# US_SB_MCU.net
KiCad netlist of a schematic drawn in Altium Designer
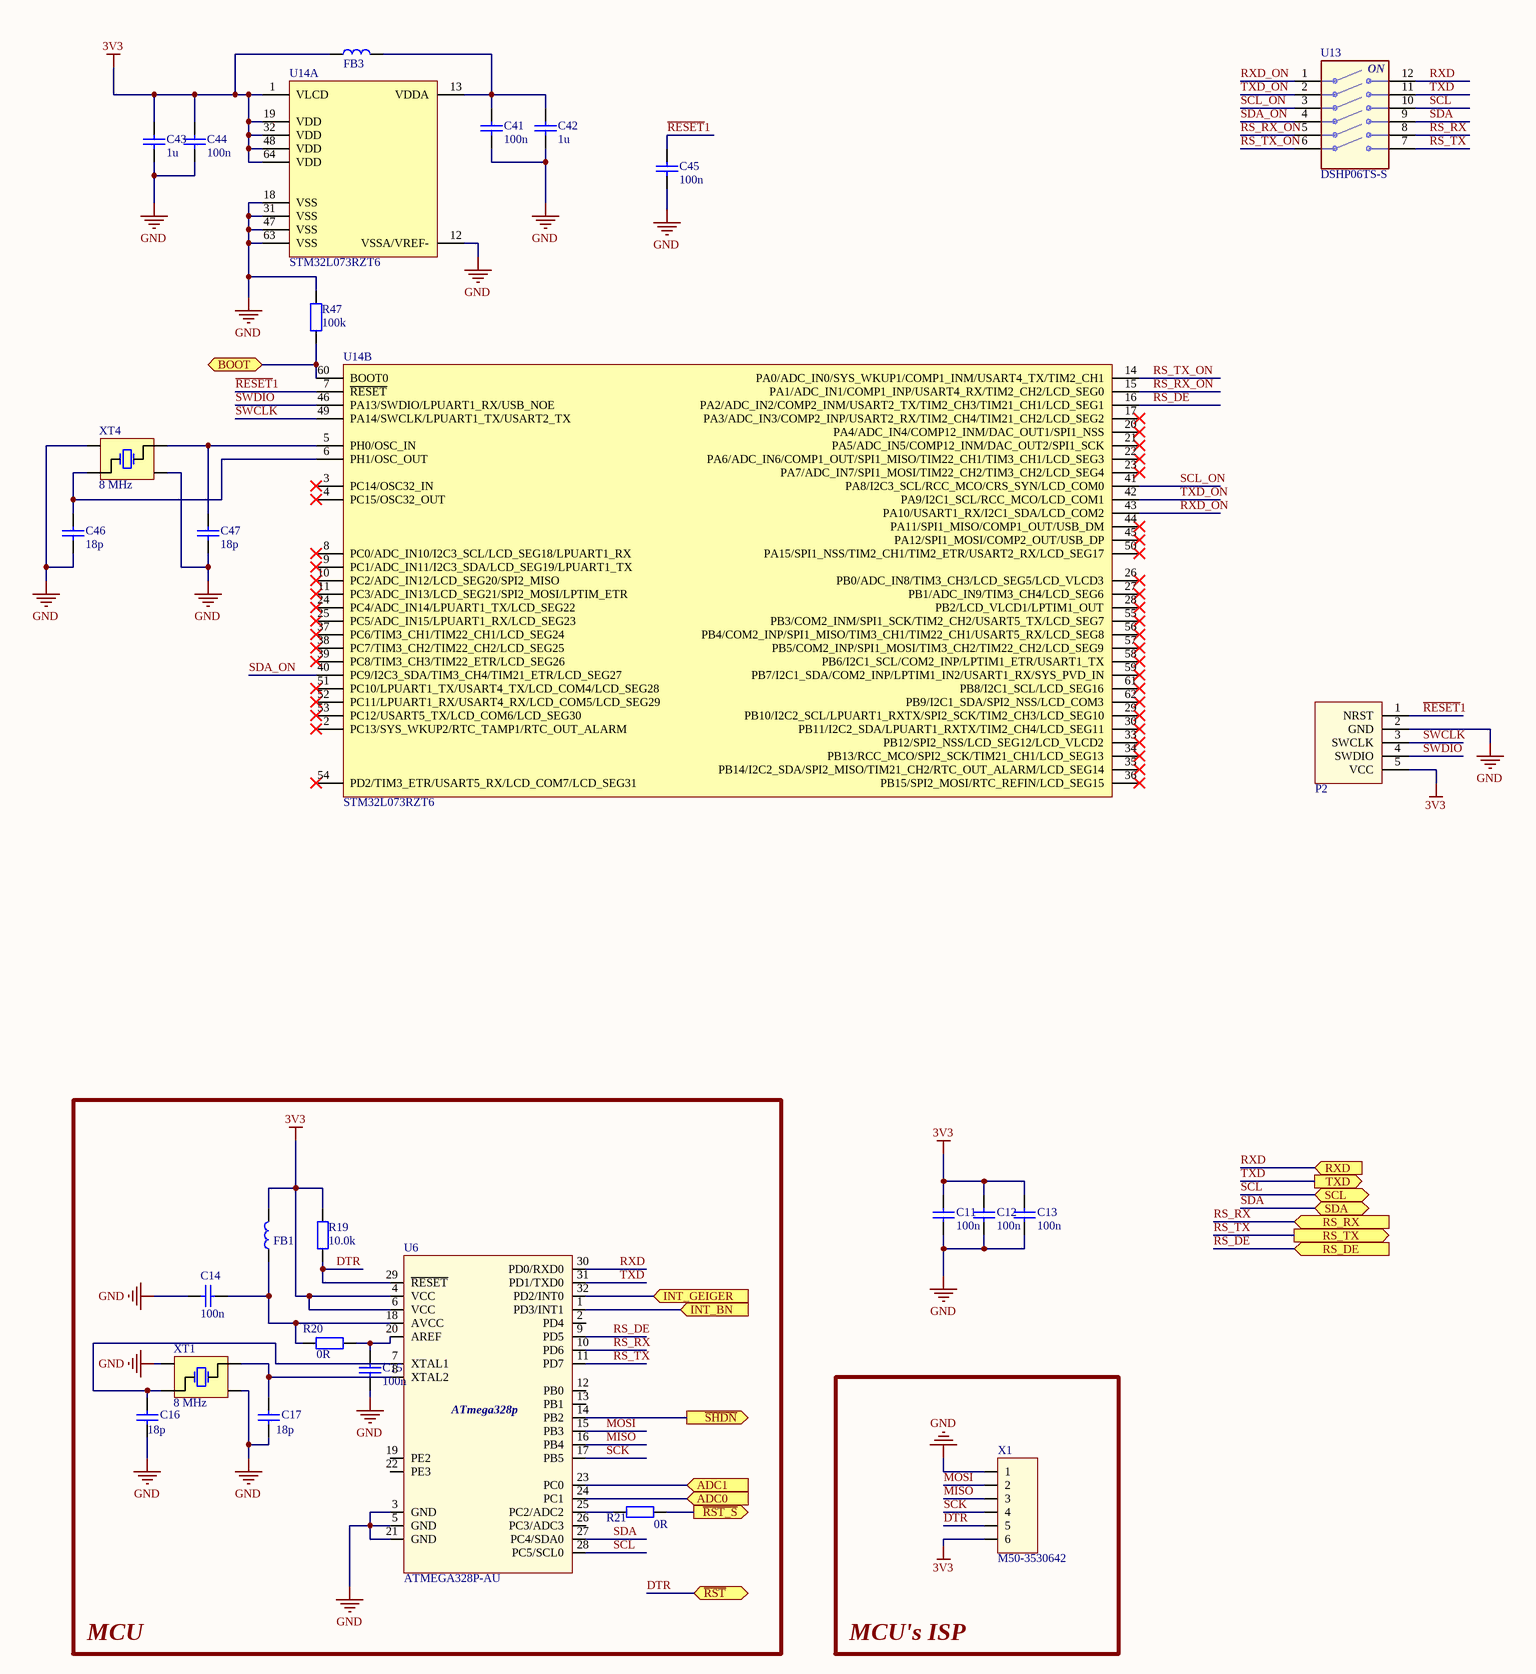
[diagram p0: US_SB_MCU.SchDoc]

(export (version "E")
  (design (tool "Eeschema 10.0.6"))
  (components
    (comp (ref "C11")
      (value "100n")
      (footprint "C0603_IPC_HD")
      (description "CAP CER 0.1UF 16V X7R 0603")
      (fields
        (field (name "MANUFACTURER") "Samsung Electro-Mechanics")
        (field (name "MANUFACTURER PART NUMBER") "CL10B104KO8NNNC")
      )
      (libsource (lib "alfasat_parts_lib") (part "CL10B104KO8NNNC"))
    )
    (comp (ref "C12")
      (value "100n")
      (footprint "C0603_IPC_HD")
      (description "CAP CER 0.1UF 16V X7R 0603")
      (fields
        (field (name "MANUFACTURER") "Samsung Electro-Mechanics")
        (field (name "MANUFACTURER PART NUMBER") "CL10B104KO8NNNC")
      )
      (libsource (lib "alfasat_parts_lib") (part "CL10B104KO8NNNC"))
    )
    (comp (ref "C13")
      (value "100n")
      (footprint "C0603_IPC_HD")
      (description "CAP CER 0.1UF 16V X7R 0603")
      (fields
        (field (name "MANUFACTURER") "Samsung Electro-Mechanics")
        (field (name "MANUFACTURER PART NUMBER") "CL10B104KO8NNNC")
      )
      (libsource (lib "alfasat_parts_lib") (part "CL10B104KO8NNNC"))
    )
    (comp (ref "C14")
      (value "100n")
      (footprint "C0603_IPC_HD")
      (description "CAP CER 0.1UF 16V X7R 0603")
      (fields
        (field (name "MANUFACTURER") "Samsung Electro-Mechanics")
        (field (name "MANUFACTURER PART NUMBER") "CL10B104KO8NNNC")
      )
      (libsource (lib "alfasat_parts_lib") (part "CL10B104KO8NNNC"))
    )
    (comp (ref "C15")
      (value "100n")
      (footprint "C0603_IPC_HD")
      (description "CAP CER 0.1UF 16V X7R 0603")
      (fields
        (field (name "MANUFACTURER") "Samsung Electro-Mechanics")
        (field (name "MANUFACTURER PART NUMBER") "CL10B104KO8NNNC")
      )
      (libsource (lib "alfasat_parts_lib") (part "CL10B104KO8NNNC"))
    )
    (comp (ref "C16")
      (value "18p")
      (footprint "C0603_IPC_HD")
      (description "CAP CER 18PF 50V C0G/NP0 0603")
      (fields
        (field (name "MANUFACTURER") "Samsung Electro-Mechanics")
        (field (name "MANUFACTURER PART NUMBER") "CL10C180JB8NNNC")
      )
      (libsource (lib "alfasat_lib") (part "CL10C180JB8NNNC"))
    )
    (comp (ref "C17")
      (value "18p")
      (footprint "C0603_IPC_HD")
      (description "CAP CER 18PF 50V C0G/NP0 0603")
      (fields
        (field (name "MANUFACTURER") "Samsung Electro-Mechanics")
        (field (name "MANUFACTURER PART NUMBER") "CL10C180JB8NNNC")
      )
      (libsource (lib "alfasat_lib") (part "CL10C180JB8NNNC"))
    )
    (comp (ref "C41")
      (value "100n")
      (footprint "C0603_IPC_HD")
      (description "CAP CER 0.1UF 16V X7R 0603")
      (fields
        (field (name "MANUFACTURER") "Samsung Electro-Mechanics")
        (field (name "MANUFACTURER PART NUMBER") "CL10B104KO8NNNC")
      )
      (libsource (lib "alfasat_parts_lib") (part "CL10B104KO8NNNC"))
    )
    (comp (ref "C42")
      (value "1u")
      (footprint "C0603_IPC_HD")
      (description "CAP CER 1UF 16V X7R 0603")
      (fields
        (field (name "MANUFACTURER") "Samsung Electro-Mechanics")
        (field (name "MANUFACTURER PART NUMBER") "CL10B105MO8NNWC")
      )
      (libsource (lib "alfasat_parts_lib") (part "CL10B105MO8NNWC"))
    )
    (comp (ref "C43")
      (value "1u")
      (footprint "C0603_IPC_HD")
      (description "CAP CER 1UF 16V X7R 0603")
      (fields
        (field (name "MANUFACTURER") "Samsung Electro-Mechanics")
        (field (name "MANUFACTURER PART NUMBER") "CL10B105MO8NNWC")
      )
      (libsource (lib "alfasat_parts_lib") (part "CL10B105MO8NNWC"))
    )
    (comp (ref "C44")
      (value "100n")
      (footprint "C0603_IPC_HD")
      (description "CAP CER 0.1UF 16V X7R 0603")
      (fields
        (field (name "MANUFACTURER") "Samsung Electro-Mechanics")
        (field (name "MANUFACTURER PART NUMBER") "CL10B104KO8NNNC")
      )
      (libsource (lib "alfasat_parts_lib") (part "CL10B104KO8NNNC"))
    )
    (comp (ref "C45")
      (value "100n")
      (footprint "C0603_IPC_HD")
      (description "CAP CER 0.1UF 16V X7R 0603")
      (fields
        (field (name "MANUFACTURER") "Samsung Electro-Mechanics")
        (field (name "MANUFACTURER PART NUMBER") "CL10B104KO8NNNC")
      )
      (libsource (lib "alfasat_parts_lib") (part "CL10B104KO8NNNC"))
    )
    (comp (ref "C46")
      (value "18p")
      (footprint "C0603_IPC_HD")
      (description "CAP CER 18PF 50V C0G/NP0 0603")
      (fields
        (field (name "MANUFACTURER") "Samsung Electro-Mechanics")
        (field (name "MANUFACTURER PART NUMBER") "CL10C180JB8NNNC")
      )
      (libsource (lib "alfasat_parts_lib") (part "CL10C180JB8NNNC"))
    )
    (comp (ref "C47")
      (value "18p")
      (footprint "C0603_IPC_HD")
      (description "CAP CER 18PF 50V C0G/NP0 0603")
      (fields
        (field (name "MANUFACTURER") "Samsung Electro-Mechanics")
        (field (name "MANUFACTURER PART NUMBER") "CL10C180JB8NNNC")
      )
      (libsource (lib "alfasat_parts_lib") (part "CL10C180JB8NNNC"))
    )
    (comp (ref "FB1")
      (value "MH1608-601Y")
      (footprint "L0603_IPC_MD")
      (description "FERRITE BEAD 600R@100MHz 0603 for Power Line, 1000mA")
      (fields (field (name "MANUFACTURER") "Bourns Inc."))
      (libsource (lib "alfasat_lib") (part "MH1608-601Y"))
    )
    (comp (ref "FB3")
      (value "MH1608-601Y")
      (footprint "L0603_IPC_MD")
      (description "FERRITE BEAD 600R@100MHz 0603 for Power Line, 1000mA")
      (fields (field (name "MANUFACTURER") "Bourns Inc."))
      (libsource (lib "alfasat_parts_lib") (part "MH1608-601Y"))
    )
    (comp (ref "P2")
      (value "SWD")
      (footprint "SWD_CON_VAR1")
      (description "SWDIO SWCLK VDD GND NRST")
      (libsource (lib "alfasat_parts_lib") (part "SWD-CONNECTOR_VAR1"))
    )
    (comp (ref "R19")
      (value "10.0k")
      (footprint "R0603_IPC_MD")
      (description "RES 10K OHM 1% 1/10W 0603")
      (fields
        (field (name "MANUFACTURER") "Stackpole Electronics Inc")
        (field (name "MANUFACTURER PART NUMBER") "RMCF0603FT10K0")
      )
      (libsource (lib "alfasat_parts_lib") (part "RMCF0603FT10K0"))
    )
    (comp (ref "R20")
      (value "0R")
      (footprint "R0603_IPC_MD")
      (description "RES SMD 0 OHM JUMPER 1/10W 0603")
      (fields
        (field (name "MANUFACTURER") "Bourns Inc.")
        (field (name "MANUFACTURER PART NUMBER") "CR0603-J/-000ELF")
      )
      (libsource (lib "alfasat_lib") (part "CR0603-J/-000ELF"))
    )
    (comp (ref "R21")
      (value "0R")
      (footprint "R0603_IPC_MD")
      (description "RES SMD 0 OHM JUMPER 1/10W 0603")
      (fields
        (field (name "MANUFACTURER") "Bourns Inc.")
        (field (name "MANUFACTURER PART NUMBER") "CR0603-J/-000ELF")
      )
      (libsource (lib "alfasat_parts_lib") (part "CR0603-J/-000ELF"))
    )
    (comp (ref "R47")
      (value "100k")
      (footprint "R0603_IPC_MD")
      (description "RES SMD 100K OHM 5% 1/10W 0603")
      (fields
        (field (name "MANUFACTURER") "Bourns Inc.")
        (field (name "MANUFACTURER PART NUMBER") "CR0603-JW-104ELF")
      )
      (libsource (lib "alfasat_parts_lib") (part "CR0603-JW-104ELF"))
    )
    (comp (ref "U6")
      (value "ATMEGA328P-AU")
      (footprint "ATmega328P_TQFP80P900X900X120-32N")
      (description "AVR AVR® ATmega Microcontroller IC 8-Bit 20MHz 32KB (16K x 16) FLASH 32-TQFP (7x7)")
      (fields (field (name "MANUFACTURER") "Microchip Technology"))
      (libsource (lib "alfasat_lib_eps") (part "ATMEGA328P-AU"))
    )
    (comp (ref "U13")
      (value "DSHP06TS-S")
      (footprint "SOIC_SW_SOIC127P850X235-12N")
      (description "SPST 6 1.27mm, Half Slide (Standard) Black SMD DIP Switches RoHS")
      (fields (field (name "MANUFACTURER") "XKB Enterprise"))
      (libsource (lib "alfasat_lib_eps") (part "DSHP06TS-S"))
    )
    (comp (ref "U14")
      (value "STM32L073RZT6")
      (footprint "LQFP64_10X10MM")
      (description "Ultra-low-power 32-bit MCU ARM®-based Cortex®-M0+")
      (fields (field (name "MANUFACTURER") "ST"))
      (libsource (lib "alfasat_parts_lib") (part "STM32L073RZT6"))
    )
    (comp (ref "X1")
      (value "M50-3530642")
      (footprint "PLS_1X6_1.27")
      (description "CONN HEADER VERT 6POS 1.27MM")
      (fields (field (name "MANUFACTURER") "Harwin Inc."))
      (libsource (lib "alfasat_lib_eps") (part "PLD_1X6_1.27"))
    )
    (comp (ref "XT1")
      (value "8 MHz")
      (footprint "5.0X3.2_4PAD_SMT")
      (description "8MHz ±10ppm Crystal 10pF 200 Ohms 4-SMD, No Lead")
      (fields
        (field (name "MANUFACTURER PART NUMBER") "ABM3B-8.000MHZ-10-1-U-T")
        (field (name "MANUFACTURER") "Abracon LLC")
      )
      (libsource (lib "alfasat_parts_lib") (part "ABM3B-8.000MHZ-10-1-U-T"))
    )
    (comp (ref "XT4")
      (value "8 MHz")
      (footprint "5.0X3.2_4PAD_SMT")
      (description "8MHz ±10ppm Crystal 10pF 200 Ohms 4-SMD, No Lead")
      (fields
        (field (name "MANUFACTURER PART NUMBER") "ABM3B-8.000MHZ-10-1-U-T")
        (field (name "MANUFACTURER") "Abracon LLC")
      )
      (libsource (lib "alfasat_parts_lib") (part "ABM3B-8.000MHZ-10-1-U-T"))
    )
  )
  (nets
    (net (code "1") (name "/ADC0") (class "Default")
      (node (ref "U6") (pin "24") (pinfunction "PC1_24") (pintype "passive"))
    )
    (net (code "2") (name "/ADC1") (class "Default")
      (node (ref "U6") (pin "23") (pinfunction "PC0_23") (pintype "passive"))
    )
    (net (code "3") (name "/BOOT") (class "Default")
      (node (ref "R47") (pin "1") (pinfunction "1_1") (pintype "passive"))
      (node (ref "U14") (pin "60") (pinfunction "BOOT0_60") (pintype "passive"))
    )
    (net (code "4") (name "/DTR") (class "Default")
      (node (ref "R19") (pin "1") (pinfunction "1_1") (pintype "passive"))
      (node (ref "U6") (pin "29") (pinfunction "~{RESET}_29") (pintype "passive"))
      (node (ref "X1") (pin "5") (pinfunction "5_5") (pintype "passive"))
    )
    (net (code "5") (name "/INT_BN") (class "Default")
      (node (ref "U6") (pin "1") (pinfunction "PD3/INT1_1") (pintype "passive"))
    )
    (net (code "6") (name "/INT_GEIGER") (class "Default")
      (node (ref "U6") (pin "32") (pinfunction "PD2/INT0_32") (pintype "passive"))
    )
    (net (code "7") (name "/MISO") (class "Default")
      (node (ref "U6") (pin "16") (pinfunction "PB4_16") (pintype "passive"))
      (node (ref "X1") (pin "3") (pinfunction "3_3") (pintype "passive"))
    )
    (net (code "8") (name "/MOSI") (class "Default")
      (node (ref "U6") (pin "15") (pinfunction "PB3_15") (pintype "passive"))
      (node (ref "X1") (pin "2") (pinfunction "2_2") (pintype "passive"))
    )
    (net (code "9") (name "/RS_DE") (class "Default")
      (node (ref "U14") (pin "16") (pinfunction "PA2/ADC_IN2/COMP2_INM/USART2_TX/TIM2_CH3/TIM21_CH1/LCD_SEG1_16") (pintype "passive"))
      (node (ref "U6") (pin "9") (pinfunction "PD5_9") (pintype "passive"))
    )
    (net (code "10") (name "/RS_RX") (class "Default")
      (node (ref "U13") (pin "8") (pinfunction "8_8") (pintype "passive"))
      (node (ref "U6") (pin "10") (pinfunction "PD6_10") (pintype "passive"))
    )
    (net (code "11") (name "/RS_RX_ON") (class "Default")
      (node (ref "U13") (pin "5") (pinfunction "5_5") (pintype "passive"))
      (node (ref "U14") (pin "15") (pinfunction "PA1/ADC_IN1/COMP1_INP/USART4_RX/TIM2_CH2/LCD_SEG0_15") (pintype "passive"))
    )
    (net (code "12") (name "/RS_TX") (class "Default")
      (node (ref "U13") (pin "7") (pinfunction "7_7") (pintype "passive"))
      (node (ref "U6") (pin "11") (pinfunction "PD7_11") (pintype "passive"))
    )
    (net (code "13") (name "/RS_TX_ON") (class "Default")
      (node (ref "U13") (pin "6") (pinfunction "6_6") (pintype "passive"))
      (node (ref "U14") (pin "14") (pinfunction "PA0/ADC_IN0/SYS_WKUP1/COMP1_INM/USART4_TX/TIM2_CH1_14") (pintype "passive"))
    )
    (net (code "14") (name "/RXD") (class "Default")
      (node (ref "U13") (pin "12") (pinfunction "12_12") (pintype "passive"))
      (node (ref "U6") (pin "30") (pinfunction "PD0/RXD0_30") (pintype "passive"))
    )
    (net (code "15") (name "/RXD_ON") (class "Default")
      (node (ref "U13") (pin "1") (pinfunction "1_1") (pintype "passive"))
      (node (ref "U14") (pin "43") (pinfunction "PA10/USART1_RX/I2C1_SDA/LCD_COM2_43") (pintype "passive"))
    )
    (net (code "16") (name "/SCK") (class "Default")
      (node (ref "U6") (pin "17") (pinfunction "PB5_17") (pintype "passive"))
      (node (ref "X1") (pin "4") (pinfunction "4_4") (pintype "passive"))
    )
    (net (code "17") (name "/SCL") (class "Default")
      (node (ref "U13") (pin "10") (pinfunction "10_10") (pintype "passive"))
      (node (ref "U6") (pin "28") (pinfunction "PC5/SCL0_28") (pintype "passive"))
    )
    (net (code "18") (name "/SCL_ON") (class "Default")
      (node (ref "U13") (pin "3") (pinfunction "3_3") (pintype "passive"))
      (node (ref "U14") (pin "41") (pinfunction "PA8/I2C3_SCL/RCC_MCO/CRS_SYN/LCD_COM0_41") (pintype "passive"))
    )
    (net (code "19") (name "/SDA") (class "Default")
      (node (ref "U13") (pin "9") (pinfunction "9_9") (pintype "passive"))
      (node (ref "U6") (pin "27") (pinfunction "PC4/SDA0_27") (pintype "passive"))
    )
    (net (code "20") (name "/SDA_ON") (class "Default")
      (node (ref "U13") (pin "4") (pinfunction "4_4") (pintype "passive"))
      (node (ref "U14") (pin "40") (pinfunction "PC9/I2C3_SDA/TIM3_CH4/TIM21_ETR/LCD_SEG27_40") (pintype "passive"))
    )
    (net (code "21") (name "/SWCLK") (class "Default")
      (node (ref "P2") (pin "3") (pinfunction "SWCLK_3") (pintype "passive"))
      (node (ref "U14") (pin "49") (pinfunction "PA14/SWCLK/LPUART1_TX/USART2_TX_49") (pintype "passive"))
    )
    (net (code "22") (name "/SWDIO") (class "Default")
      (node (ref "P2") (pin "4") (pinfunction "SWDIO_4") (pintype "passive"))
      (node (ref "U14") (pin "46") (pinfunction "PA13/SWDIO/LPUART1_RX/USB_NOE_46") (pintype "passive"))
    )
    (net (code "23") (name "/TXD") (class "Default")
      (node (ref "U13") (pin "11") (pinfunction "11_11") (pintype "passive"))
      (node (ref "U6") (pin "31") (pinfunction "PD1/TXD0_31") (pintype "passive"))
    )
    (net (code "24") (name "/TXD_ON") (class "Default")
      (node (ref "U13") (pin "2") (pinfunction "2_2") (pintype "passive"))
      (node (ref "U14") (pin "42") (pinfunction "PA9/I2C1_SCL/RCC_MCO/LCD_COM1_42") (pintype "passive"))
    )
    (net (code "25") (name "/~{RESET}1") (class "Default")
      (node (ref "C45") (pin "1") (pinfunction "1_1") (pintype "passive"))
      (node (ref "P2") (pin "1") (pinfunction "NRST_1") (pintype "passive"))
      (node (ref "U14") (pin "7") (pinfunction "~{RESET}_7") (pintype "passive"))
    )
    (net (code "26") (name "/~{RST_S}") (class "Default")
      (node (ref "R21") (pin "2") (pinfunction "2_2") (pintype "passive"))
    )
    (net (code "27") (name "/~{SHDN}") (class "Default")
      (node (ref "U6") (pin "14") (pinfunction "PB2_14") (pintype "passive"))
    )
    (net (code "28") (name "3V3") (class "Default")
      (node (ref "C11") (pin "1") (pinfunction "1_1") (pintype "passive"))
      (node (ref "C12") (pin "1") (pinfunction "1_1") (pintype "passive"))
      (node (ref "C13") (pin "1") (pinfunction "1_1") (pintype "passive"))
      (node (ref "C43") (pin "2") (pinfunction "2_2") (pintype "passive"))
      (node (ref "C44") (pin "2") (pinfunction "2_2") (pintype "passive"))
      (node (ref "FB1") (pin "2") (pinfunction "2_2") (pintype "passive"))
      (node (ref "FB3") (pin "1") (pinfunction "1_1") (pintype "passive"))
      (node (ref "P2") (pin "5") (pinfunction "VCC_5") (pintype "passive"))
      (node (ref "R19") (pin "2") (pinfunction "2_2") (pintype "passive"))
      (node (ref "U14") (pin "1") (pinfunction "VLCD_1") (pintype "power_in"))
      (node (ref "U14") (pin "19") (pinfunction "VDD_19") (pintype "power_in"))
      (node (ref "U14") (pin "32") (pinfunction "VDD_32") (pintype "power_in"))
      (node (ref "U14") (pin "48") (pinfunction "VDD_48") (pintype "power_in"))
      (node (ref "U14") (pin "64") (pinfunction "VDD_64") (pintype "power_in"))
      (node (ref "U6") (pin "4") (pinfunction "VCC_4") (pintype "passive"))
      (node (ref "U6") (pin "6") (pinfunction "VCC_6") (pintype "passive"))
      (node (ref "X1") (pin "6") (pinfunction "6_6") (pintype "passive"))
    )
    (net (code "29") (name "GND") (class "Default")
      (node (ref "C11") (pin "2") (pinfunction "2_2") (pintype "passive"))
      (node (ref "C12") (pin "2") (pinfunction "2_2") (pintype "passive"))
      (node (ref "C13") (pin "2") (pinfunction "2_2") (pintype "passive"))
      (node (ref "C14") (pin "2") (pinfunction "2_2") (pintype "passive"))
      (node (ref "C15") (pin "2") (pinfunction "2_2") (pintype "passive"))
      (node (ref "C16") (pin "1") (pinfunction "1_1") (pintype "passive"))
      (node (ref "C17") (pin "1") (pinfunction "1_1") (pintype "passive"))
      (node (ref "C41") (pin "1") (pinfunction "1_1") (pintype "passive"))
      (node (ref "C42") (pin "1") (pinfunction "1_1") (pintype "passive"))
      (node (ref "C43") (pin "1") (pinfunction "1_1") (pintype "passive"))
      (node (ref "C44") (pin "1") (pinfunction "1_1") (pintype "passive"))
      (node (ref "C45") (pin "2") (pinfunction "2_2") (pintype "passive"))
      (node (ref "C46") (pin "1") (pinfunction "1_1") (pintype "passive"))
      (node (ref "C47") (pin "1") (pinfunction "1_1") (pintype "passive"))
      (node (ref "P2") (pin "2") (pinfunction "GND_2") (pintype "passive"))
      (node (ref "R47") (pin "2") (pinfunction "2_2") (pintype "passive"))
      (node (ref "U14") (pin "12") (pinfunction "VSSA/VREF-_12") (pintype "power_in"))
      (node (ref "U14") (pin "18") (pinfunction "VSS_18") (pintype "power_in"))
      (node (ref "U14") (pin "31") (pinfunction "VSS_31") (pintype "power_in"))
      (node (ref "U14") (pin "47") (pinfunction "VSS_47") (pintype "power_in"))
      (node (ref "U14") (pin "63") (pinfunction "VSS_63") (pintype "power_in"))
      (node (ref "U6") (pin "21") (pinfunction "GND_21") (pintype "passive"))
      (node (ref "U6") (pin "3") (pinfunction "GND_3") (pintype "passive"))
      (node (ref "U6") (pin "5") (pinfunction "GND_5") (pintype "passive"))
      (node (ref "X1") (pin "1") (pinfunction "1_1") (pintype "passive"))
      (node (ref "XT1") (pin "2") (pinfunction "NC_2") (pintype "passive"))
      (node (ref "XT1") (pin "4") (pinfunction "NC_4") (pintype "passive"))
      (node (ref "XT4") (pin "2") (pinfunction "NC_2") (pintype "passive"))
      (node (ref "XT4") (pin "4") (pinfunction "NC_4") (pintype "passive"))
    )
    (net (code "30") (name "Net-(U6-AREF)") (class "Default")
      (node (ref "C15") (pin "1") (pinfunction "1_1") (pintype "passive"))
      (node (ref "R20") (pin "2") (pinfunction "2_2") (pintype "passive"))
      (node (ref "U6") (pin "20") (pinfunction "AREF_20") (pintype "passive"))
    )
    (net (code "31") (name "Net-(U6-AVCC)") (class "Default")
      (node (ref "C14") (pin "1") (pinfunction "1_1") (pintype "passive"))
      (node (ref "FB1") (pin "1") (pinfunction "1_1") (pintype "passive"))
      (node (ref "R20") (pin "1") (pinfunction "1_1") (pintype "passive"))
      (node (ref "U6") (pin "18") (pinfunction "AVCC_18") (pintype "passive"))
    )
    (net (code "32") (name "Net-(U6-PC2{slash}ADC2)") (class "Default")
      (node (ref "R21") (pin "1") (pinfunction "1_1") (pintype "passive"))
      (node (ref "U6") (pin "25") (pinfunction "PC2/ADC2_25") (pintype "passive"))
    )
    (net (code "33") (name "Net-(U6-XTAL1)") (class "Default")
      (node (ref "C16") (pin "2") (pinfunction "2_2") (pintype "passive"))
      (node (ref "U6") (pin "7") (pinfunction "XTAL1_7") (pintype "passive"))
      (node (ref "XT1") (pin "3") (pinfunction "OSC2_3") (pintype "passive"))
    )
    (net (code "34") (name "Net-(U6-XTAL2)") (class "Default")
      (node (ref "C17") (pin "2") (pinfunction "2_2") (pintype "passive"))
      (node (ref "U6") (pin "8") (pinfunction "XTAL2_8") (pintype "passive"))
      (node (ref "XT1") (pin "1") (pinfunction "OSC1_1") (pintype "passive"))
    )
    (net (code "35") (name "Net-(U14A-VDDA)") (class "Default")
      (node (ref "C41") (pin "2") (pinfunction "2_2") (pintype "passive"))
      (node (ref "C42") (pin "2") (pinfunction "2_2") (pintype "passive"))
      (node (ref "FB3") (pin "2") (pinfunction "2_2") (pintype "passive"))
      (node (ref "U14") (pin "13") (pinfunction "VDDA_13") (pintype "power_in"))
    )
    (net (code "36") (name "Net-(U14B-PH0{slash}OSC_IN)") (class "Default")
      (node (ref "C47") (pin "2") (pinfunction "2_2") (pintype "passive"))
      (node (ref "U14") (pin "5") (pinfunction "PH0/OSC_IN_5") (pintype "passive"))
      (node (ref "XT4") (pin "1") (pinfunction "OSC1_1") (pintype "passive"))
    )
    (net (code "37") (name "Net-(U14B-PH1{slash}OSC_OUT)") (class "Default")
      (node (ref "C46") (pin "2") (pinfunction "2_2") (pintype "passive"))
      (node (ref "U14") (pin "6") (pinfunction "PH1/OSC_OUT_6") (pintype "passive"))
      (node (ref "XT4") (pin "3") (pinfunction "OSC2_3") (pintype "passive"))
    )
    (net (code "38") (name "unconnected-(U6-PB0-Pad12)") (class "Default")
      (node (ref "U6") (pin "12") (pinfunction "PB0_12") (pintype "passive"))
    )
    (net (code "39") (name "unconnected-(U6-PB1-Pad13)") (class "Default")
      (node (ref "U6") (pin "13") (pinfunction "PB1_13") (pintype "passive"))
    )
    (net (code "40") (name "unconnected-(U6-PC3{slash}ADC3-Pad26)") (class "Default")
      (node (ref "U6") (pin "26") (pinfunction "PC3/ADC3_26") (pintype "passive"))
    )
    (net (code "41") (name "unconnected-(U6-PD4-Pad2)") (class "Default")
      (node (ref "U6") (pin "2") (pinfunction "PD4_2") (pintype "passive"))
    )
    (net (code "42") (name "unconnected-(U6-PE2-Pad19)") (class "Default")
      (node (ref "U6") (pin "19") (pinfunction "PE2_19") (pintype "passive"))
    )
    (net (code "43") (name "unconnected-(U6-PE3-Pad22)") (class "Default")
      (node (ref "U6") (pin "22") (pinfunction "PE3_22") (pintype "passive"))
    )
    (net (code "44") (name "unconnected-(U14B-PA3{slash}ADC_IN3{slash}COMP2_INP{slash}USART2_RX{slash}TIM2_CH4{slash}TIM21_CH2{slash}LCD_SEG2-Pad17)") (class "Default")
      (node (ref "U14") (pin "17") (pinfunction "PA3/ADC_IN3/COMP2_INP/USART2_RX/TIM2_CH4/TIM21_CH2/LCD_SEG2_17") (pintype "passive+no_connect"))
    )
    (net (code "45") (name "unconnected-(U14B-PA4{slash}ADC_IN4{slash}COMP12_INM{slash}DAC_OUT1{slash}SPI1_NSS-Pad20)") (class "Default")
      (node (ref "U14") (pin "20") (pinfunction "PA4/ADC_IN4/COMP12_INM/DAC_OUT1/SPI1_NSS_20") (pintype "passive+no_connect"))
    )
    (net (code "46") (name "unconnected-(U14B-PA5{slash}ADC_IN5{slash}COMP12_INM{slash}DAC_OUT2{slash}SPI1_SCK-Pad21)") (class "Default")
      (node (ref "U14") (pin "21") (pinfunction "PA5/ADC_IN5/COMP12_INM/DAC_OUT2/SPI1_SCK_21") (pintype "passive+no_connect"))
    )
    (net (code "47") (name "unconnected-(U14B-PA6{slash}ADC_IN6{slash}COMP1_OUT{slash}SPI1_MISO{slash}TIM22_CH1{slash}TIM3_CH1{slash}LCD_SEG3-Pad22)") (class "Default")
      (node (ref "U14") (pin "22") (pinfunction "PA6/ADC_IN6/COMP1_OUT/SPI1_MISO/TIM22_CH1/TIM3_CH1/LCD_SEG3_22") (pintype "passive+no_connect"))
    )
    (net (code "48") (name "unconnected-(U14B-PA7{slash}ADC_IN7{slash}SPI1_MOSI{slash}TIM22_CH2{slash}TIM3_CH2{slash}LCD_SEG4-Pad23)") (class "Default")
      (node (ref "U14") (pin "23") (pinfunction "PA7/ADC_IN7/SPI1_MOSI/TIM22_CH2/TIM3_CH2/LCD_SEG4_23") (pintype "passive+no_connect"))
    )
    (net (code "49") (name "unconnected-(U14B-PA11{slash}SPI1_MISO{slash}COMP1_OUT{slash}USB_DM-Pad44)") (class "Default")
      (node (ref "U14") (pin "44") (pinfunction "PA11/SPI1_MISO/COMP1_OUT/USB_DM_44") (pintype "passive+no_connect"))
    )
    (net (code "50") (name "unconnected-(U14B-PA12{slash}SPI1_MOSI{slash}COMP2_OUT{slash}USB_DP-Pad45)") (class "Default")
      (node (ref "U14") (pin "45") (pinfunction "PA12/SPI1_MOSI/COMP2_OUT/USB_DP_45") (pintype "passive+no_connect"))
    )
    (net (code "51") (name "unconnected-(U14B-PA15{slash}SPI1_NSS{slash}TIM2_CH1{slash}TIM2_ETR{slash}USART2_RX{slash}LCD_SEG17-Pad50)") (class "Default")
      (node (ref "U14") (pin "50") (pinfunction "PA15/SPI1_NSS/TIM2_CH1/TIM2_ETR/USART2_RX/LCD_SEG17_50") (pintype "passive+no_connect"))
    )
    (net (code "52") (name "unconnected-(U14B-PB0{slash}ADC_IN8{slash}TIM3_CH3{slash}LCD_SEG5{slash}LCD_VLCD3-Pad26)") (class "Default")
      (node (ref "U14") (pin "26") (pinfunction "PB0/ADC_IN8/TIM3_CH3/LCD_SEG5/LCD_VLCD3_26") (pintype "passive+no_connect"))
    )
    (net (code "53") (name "unconnected-(U14B-PB1{slash}ADC_IN9{slash}TIM3_CH4{slash}LCD_SEG6-Pad27)") (class "Default")
      (node (ref "U14") (pin "27") (pinfunction "PB1/ADC_IN9/TIM3_CH4/LCD_SEG6_27") (pintype "passive+no_connect"))
    )
    (net (code "54") (name "unconnected-(U14B-PB2{slash}LCD_VLCD1{slash}LPTIM1_OUT-Pad28)") (class "Default")
      (node (ref "U14") (pin "28") (pinfunction "PB2/LCD_VLCD1/LPTIM1_OUT_28") (pintype "passive+no_connect"))
    )
    (net (code "55") (name "unconnected-(U14B-PB3{slash}COM2_INM{slash}SPI1_SCK{slash}TIM2_CH2{slash}USART5_TX{slash}LCD_SEG7-Pad55)") (class "Default")
      (node (ref "U14") (pin "55") (pinfunction "PB3/COM2_INM/SPI1_SCK/TIM2_CH2/USART5_TX/LCD_SEG7_55") (pintype "passive+no_connect"))
    )
    (net (code "56") (name "unconnected-(U14B-PB4{slash}COM2_INP{slash}SPI1_MISO{slash}TIM3_CH1{slash}TIM22_CH1{slash}USART5_RX{slash}LCD_SEG8-Pad56)") (class "Default")
      (node (ref "U14") (pin "56") (pinfunction "PB4/COM2_INP/SPI1_MISO/TIM3_CH1/TIM22_CH1/USART5_RX/LCD_SEG8_56") (pintype "passive+no_connect"))
    )
    (net (code "57") (name "unconnected-(U14B-PB5{slash}COM2_INP{slash}SPI1_MOSI{slash}TIM3_CH2{slash}TIM22_CH2{slash}LCD_SEG9-Pad57)") (class "Default")
      (node (ref "U14") (pin "57") (pinfunction "PB5/COM2_INP/SPI1_MOSI/TIM3_CH2/TIM22_CH2/LCD_SEG9_57") (pintype "passive+no_connect"))
    )
    (net (code "58") (name "unconnected-(U14B-PB6{slash}I2C1_SCL{slash}COM2_INP{slash}LPTIM1_ETR{slash}USART1_TX-Pad58)") (class "Default")
      (node (ref "U14") (pin "58") (pinfunction "PB6/I2C1_SCL/COM2_INP/LPTIM1_ETR/USART1_TX_58") (pintype "passive+no_connect"))
    )
    (net (code "59") (name "unconnected-(U14B-PB7{slash}I2C1_SDA{slash}COM2_INP{slash}LPTIM1_IN2{slash}USART1_RX{slash}SYS_PVD_IN-Pad59)") (class "Default")
      (node (ref "U14") (pin "59") (pinfunction "PB7/I2C1_SDA/COM2_INP/LPTIM1_IN2/USART1_RX/SYS_PVD_IN_59") (pintype "passive+no_connect"))
    )
    (net (code "60") (name "unconnected-(U14B-PB8{slash}I2C1_SCL{slash}LCD_SEG16-Pad61)") (class "Default")
      (node (ref "U14") (pin "61") (pinfunction "PB8/I2C1_SCL/LCD_SEG16_61") (pintype "passive+no_connect"))
    )
    (net (code "61") (name "unconnected-(U14B-PB9{slash}I2C1_SDA{slash}SPI2_NSS{slash}LCD_COM3-Pad62)") (class "Default")
      (node (ref "U14") (pin "62") (pinfunction "PB9/I2C1_SDA/SPI2_NSS/LCD_COM3_62") (pintype "passive+no_connect"))
    )
    (net (code "62") (name "unconnected-(U14B-PB10{slash}I2C2_SCL{slash}LPUART1_RXTX{slash}SPI2_SCK{slash}TIM2_CH3{slash}LCD_SEG10-Pad29)") (class "Default")
      (node (ref "U14") (pin "29") (pinfunction "PB10/I2C2_SCL/LPUART1_RXTX/SPI2_SCK/TIM2_CH3/LCD_SEG10_29") (pintype "passive+no_connect"))
    )
    (net (code "63") (name "unconnected-(U14B-PB11{slash}I2C2_SDA{slash}LPUART1_RXTX{slash}TIM2_CH4{slash}LCD_SEG11-Pad30)") (class "Default")
      (node (ref "U14") (pin "30") (pinfunction "PB11/I2C2_SDA/LPUART1_RXTX/TIM2_CH4/LCD_SEG11_30") (pintype "passive+no_connect"))
    )
    (net (code "64") (name "unconnected-(U14B-PB12{slash}SPI2_NSS{slash}LCD_SEG12{slash}LCD_VLCD2-Pad33)") (class "Default")
      (node (ref "U14") (pin "33") (pinfunction "PB12/SPI2_NSS/LCD_SEG12/LCD_VLCD2_33") (pintype "passive+no_connect"))
    )
    (net (code "65") (name "unconnected-(U14B-PB13{slash}RCC_MCO{slash}SPI2_SCK{slash}TIM21_CH1{slash}LCD_SEG13-Pad34)") (class "Default")
      (node (ref "U14") (pin "34") (pinfunction "PB13/RCC_MCO/SPI2_SCK/TIM21_CH1/LCD_SEG13_34") (pintype "passive+no_connect"))
    )
    (net (code "66") (name "unconnected-(U14B-PB14{slash}I2C2_SDA{slash}SPI2_MISO{slash}TIM21_CH2{slash}RTC_OUT_ALARM{slash}LCD_SEG14-Pad35)") (class "Default")
      (node (ref "U14") (pin "35") (pinfunction "PB14/I2C2_SDA/SPI2_MISO/TIM21_CH2/RTC_OUT_ALARM/LCD_SEG14_35") (pintype "passive+no_connect"))
    )
    (net (code "67") (name "unconnected-(U14B-PB15{slash}SPI2_MOSI{slash}RTC_REFIN{slash}LCD_SEG15-Pad36)") (class "Default")
      (node (ref "U14") (pin "36") (pinfunction "PB15/SPI2_MOSI/RTC_REFIN/LCD_SEG15_36") (pintype "passive+no_connect"))
    )
    (net (code "68") (name "unconnected-(U14B-PC0{slash}ADC_IN10{slash}I2C3_SCL{slash}LCD_SEG18{slash}LPUART1_RX-Pad8)") (class "Default")
      (node (ref "U14") (pin "8") (pinfunction "PC0/ADC_IN10/I2C3_SCL/LCD_SEG18/LPUART1_RX_8") (pintype "passive+no_connect"))
    )
    (net (code "69") (name "unconnected-(U14B-PC1{slash}ADC_IN11{slash}I2C3_SDA{slash}LCD_SEG19{slash}LPUART1_TX-Pad9)") (class "Default")
      (node (ref "U14") (pin "9") (pinfunction "PC1/ADC_IN11/I2C3_SDA/LCD_SEG19/LPUART1_TX_9") (pintype "passive+no_connect"))
    )
    (net (code "70") (name "unconnected-(U14B-PC2{slash}ADC_IN12{slash}LCD_SEG20{slash}SPI2_MISO-Pad10)") (class "Default")
      (node (ref "U14") (pin "10") (pinfunction "PC2/ADC_IN12/LCD_SEG20/SPI2_MISO_10") (pintype "passive+no_connect"))
    )
    (net (code "71") (name "unconnected-(U14B-PC3{slash}ADC_IN13{slash}LCD_SEG21{slash}SPI2_MOSI{slash}LPTIM_ETR-Pad11)") (class "Default")
      (node (ref "U14") (pin "11") (pinfunction "PC3/ADC_IN13/LCD_SEG21/SPI2_MOSI/LPTIM_ETR_11") (pintype "passive+no_connect"))
    )
    (net (code "72") (name "unconnected-(U14B-PC4{slash}ADC_IN14{slash}LPUART1_TX{slash}LCD_SEG22-Pad24)") (class "Default")
      (node (ref "U14") (pin "24") (pinfunction "PC4/ADC_IN14/LPUART1_TX/LCD_SEG22_24") (pintype "passive+no_connect"))
    )
    (net (code "73") (name "unconnected-(U14B-PC5{slash}ADC_IN15{slash}LPUART1_RX{slash}LCD_SEG23-Pad25)") (class "Default")
      (node (ref "U14") (pin "25") (pinfunction "PC5/ADC_IN15/LPUART1_RX/LCD_SEG23_25") (pintype "passive+no_connect"))
    )
    (net (code "74") (name "unconnected-(U14B-PC6{slash}TIM3_CH1{slash}TIM22_CH1{slash}LCD_SEG24-Pad37)") (class "Default")
      (node (ref "U14") (pin "37") (pinfunction "PC6/TIM3_CH1/TIM22_CH1/LCD_SEG24_37") (pintype "passive+no_connect"))
    )
    (net (code "75") (name "unconnected-(U14B-PC7{slash}TIM3_CH2{slash}TIM22_CH2{slash}LCD_SEG25-Pad38)") (class "Default")
      (node (ref "U14") (pin "38") (pinfunction "PC7/TIM3_CH2/TIM22_CH2/LCD_SEG25_38") (pintype "passive+no_connect"))
    )
    (net (code "76") (name "unconnected-(U14B-PC8{slash}TIM3_CH3{slash}TIM22_ETR{slash}LCD_SEG26-Pad39)") (class "Default")
      (node (ref "U14") (pin "39") (pinfunction "PC8/TIM3_CH3/TIM22_ETR/LCD_SEG26_39") (pintype "passive+no_connect"))
    )
    (net (code "77") (name "unconnected-(U14B-PC10{slash}LPUART1_TX{slash}USART4_TX{slash}LCD_COM4{slash}LCD_SEG28-Pad51)") (class "Default")
      (node (ref "U14") (pin "51") (pinfunction "PC10/LPUART1_TX/USART4_TX/LCD_COM4/LCD_SEG28_51") (pintype "passive+no_connect"))
    )
    (net (code "78") (name "unconnected-(U14B-PC11{slash}LPUART1_RX{slash}USART4_RX{slash}LCD_COM5{slash}LCD_SEG29-Pad52)") (class "Default")
      (node (ref "U14") (pin "52") (pinfunction "PC11/LPUART1_RX/USART4_RX/LCD_COM5/LCD_SEG29_52") (pintype "passive+no_connect"))
    )
    (net (code "79") (name "unconnected-(U14B-PC12{slash}USART5_TX{slash}LCD_COM6{slash}LCD_SEG30-Pad53)") (class "Default")
      (node (ref "U14") (pin "53") (pinfunction "PC12/USART5_TX/LCD_COM6/LCD_SEG30_53") (pintype "passive+no_connect"))
    )
    (net (code "80") (name "unconnected-(U14B-PC13{slash}SYS_WKUP2{slash}RTC_TAMP1{slash}RTC_OUT_ALARM-Pad2)") (class "Default")
      (node (ref "U14") (pin "2") (pinfunction "PC13/SYS_WKUP2/RTC_TAMP1/RTC_OUT_ALARM_2") (pintype "passive+no_connect"))
    )
    (net (code "81") (name "unconnected-(U14B-PC14{slash}OSC32_IN-Pad3)") (class "Default")
      (node (ref "U14") (pin "3") (pinfunction "PC14/OSC32_IN_3") (pintype "passive+no_connect"))
    )
    (net (code "82") (name "unconnected-(U14B-PC15{slash}OSC32_OUT-Pad4)") (class "Default")
      (node (ref "U14") (pin "4") (pinfunction "PC15/OSC32_OUT_4") (pintype "passive+no_connect"))
    )
    (net (code "83") (name "unconnected-(U14B-PD2{slash}TIM3_ETR{slash}USART5_RX{slash}LCD_COM7{slash}LCD_SEG31-Pad54)") (class "Default")
      (node (ref "U14") (pin "54") (pinfunction "PD2/TIM3_ETR/USART5_RX/LCD_COM7/LCD_SEG31_54") (pintype "passive+no_connect"))
    )
  )
)
